# Modulo_de_expansao_01.net
KiCad netlist of a schematic drawn in EAGLE
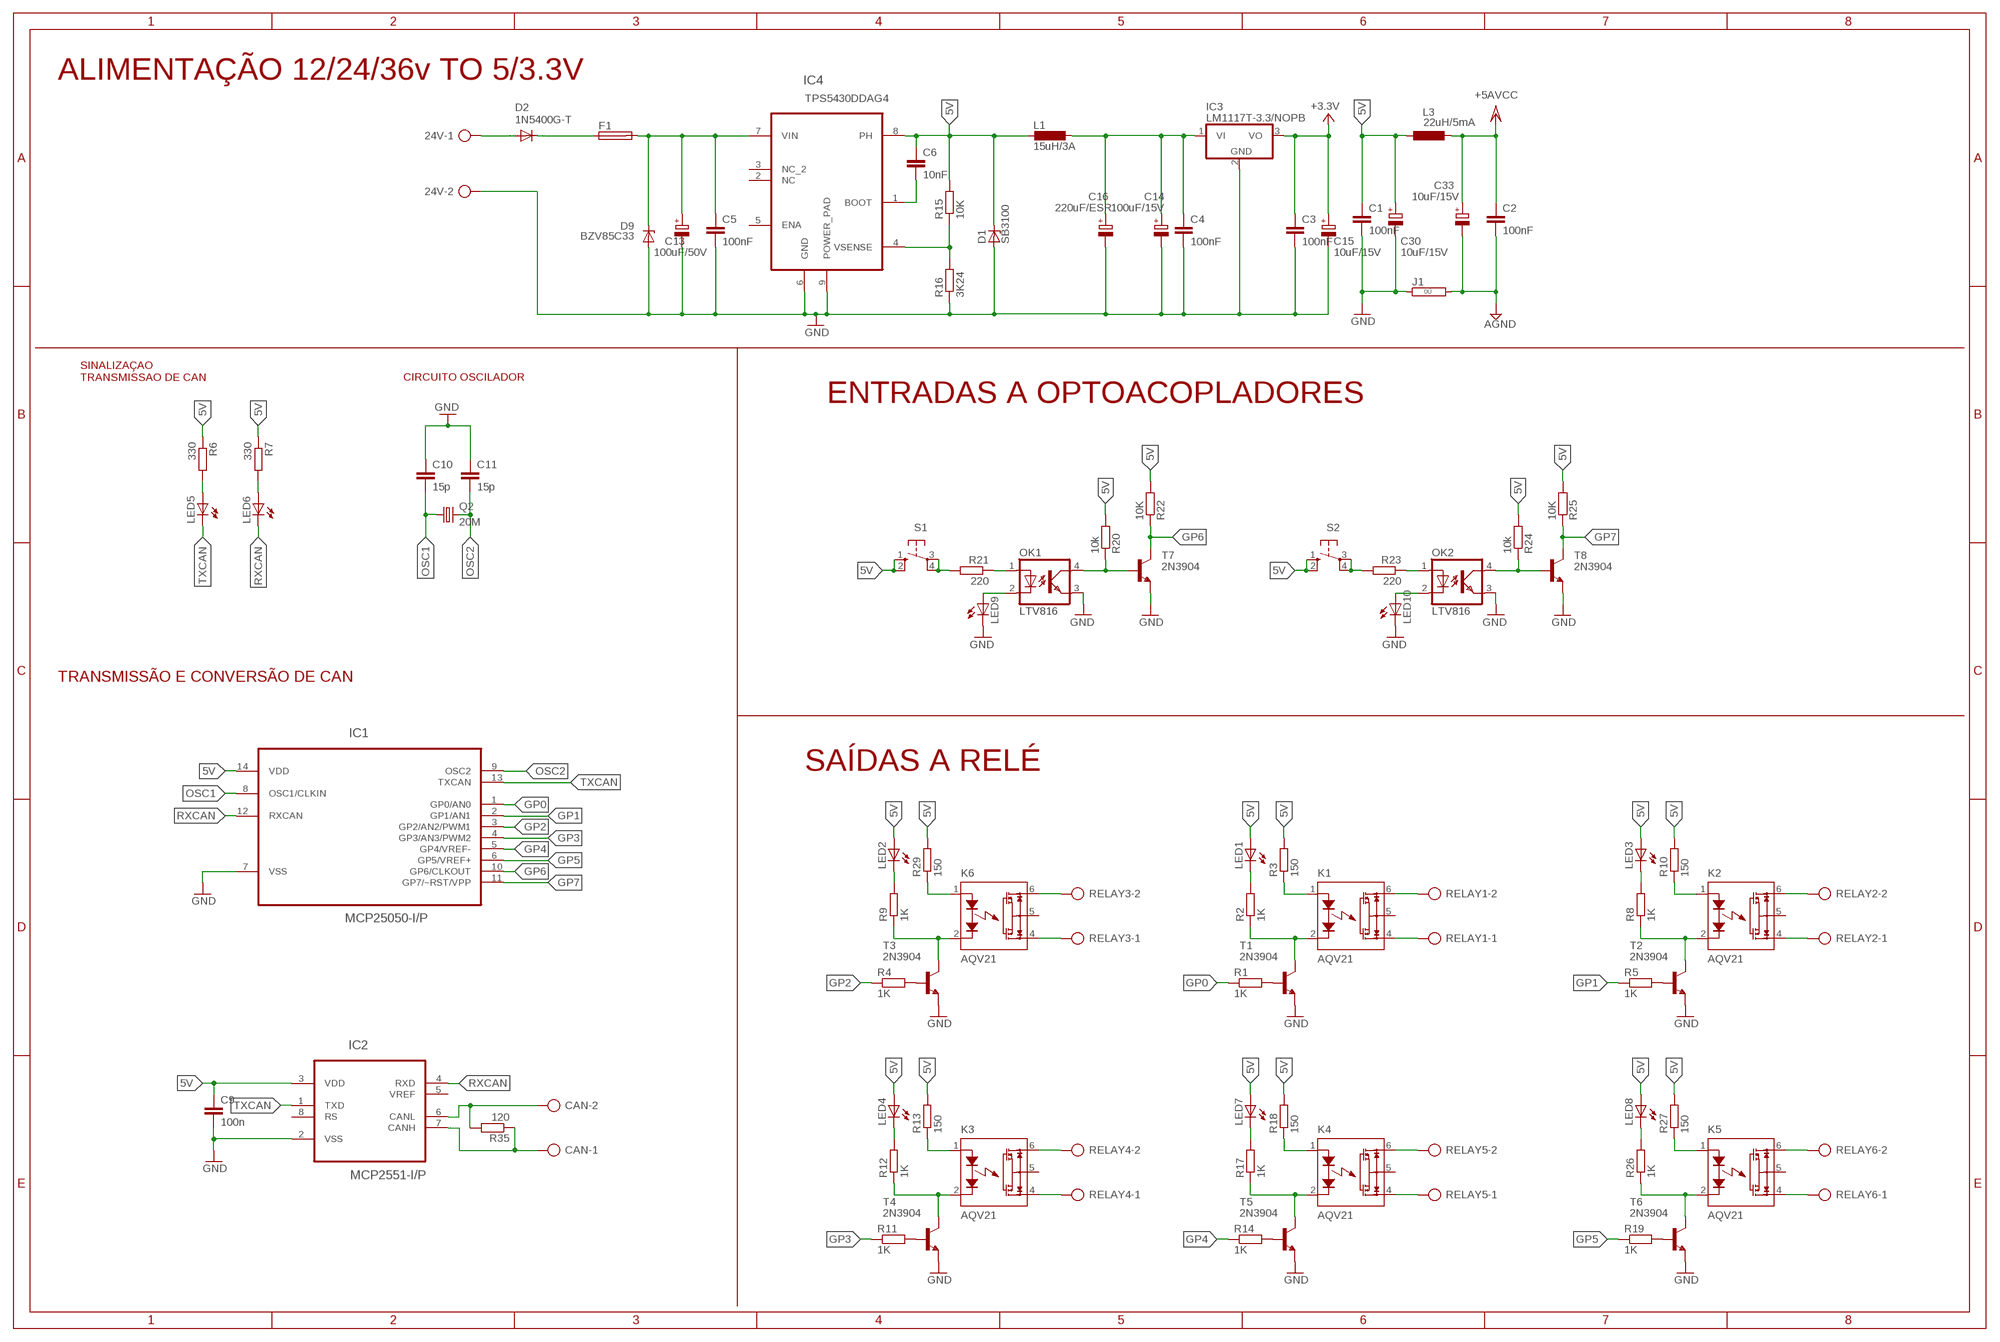
[diagram p0: schematic, sheet 1]

(export (version "E")
  (design (tool "Eeschema 10.0.6"))
  (components
    (comp (ref "24V")
      (value "AK300/2")
      (footprint "eagle-import:AK300_2")
      (libsource (lib "eagle-import") (part "AK300/2"))
    )
    (comp (ref "C1")
      (value "100nF")
      (footprint "eagle-import:C050-024X044")
      (libsource (lib "eagle-import") (part "C-EU050-024X044"))
    )
    (comp (ref "C2")
      (value "100nF")
      (footprint "eagle-import:C050-024X044")
      (libsource (lib "eagle-import") (part "C-EU050-024X044"))
    )
    (comp (ref "C3")
      (value "100nF")
      (footprint "eagle-import:C050-024X044")
      (libsource (lib "eagle-import") (part "C-EU050-024X044"))
    )
    (comp (ref "C4")
      (value "100nF")
      (footprint "eagle-import:C050-024X044")
      (libsource (lib "eagle-import") (part "C-EU050-024X044"))
    )
    (comp (ref "C5")
      (value "100nF")
      (footprint "eagle-import:C050-024X044")
      (libsource (lib "eagle-import") (part "C-EU050-024X044"))
    )
    (comp (ref "C6")
      (value "10nF")
      (footprint "eagle-import:C025-025X050")
      (libsource (lib "eagle-import") (part "C-EU025-025X050"))
    )
    (comp (ref "C9")
      (value "100n")
      (footprint "eagle-import:C050-024X044")
      (libsource (lib "eagle-import") (part "C-EU050-024X044"))
    )
    (comp (ref "C10")
      (value "15p")
      (footprint "eagle-import:C025-024X044")
      (libsource (lib "eagle-import") (part "C-EU025-024X044"))
    )
    (comp (ref "C11")
      (value "15p")
      (footprint "eagle-import:C025-024X044")
      (libsource (lib "eagle-import") (part "C-EU025-024X044"))
    )
    (comp (ref "C13")
      (value "100uF/50V")
      (footprint "eagle-import:E3,5-10")
      (libsource (lib "eagle-import") (part "CPOL-EUE3.5-10"))
    )
    (comp (ref "C14")
      (value "100uF/15V")
      (footprint "eagle-import:E2-5")
      (libsource (lib "eagle-import") (part "CPOL-EUE2-5"))
    )
    (comp (ref "C15")
      (value "10uF/15V")
      (footprint "eagle-import:E2-5")
      (libsource (lib "eagle-import") (part "CPOL-EUE2-5"))
    )
    (comp (ref "C16")
      (value "220uF/ESR")
      (footprint "eagle-import:E2,5-7")
      (libsource (lib "eagle-import") (part "CPOL-EUE2.5-7"))
    )
    (comp (ref "C30")
      (value "10uF/15V")
      (footprint "eagle-import:E2,5-6")
      (libsource (lib "eagle-import") (part "CPOL-EUE2.5-6"))
    )
    (comp (ref "C33")
      (value "10uF/15V")
      (footprint "eagle-import:E2,5-6")
      (libsource (lib "eagle-import") (part "CPOL-EUE2.5-6"))
    )
    (comp (ref "CAN")
      (value "AK300/2")
      (footprint "eagle-import:AK300_2")
      (libsource (lib "eagle-import") (part "AK300/2"))
    )
    (comp (ref "D1")
      (value "SB3100")
      (footprint "eagle-import:DO34Z7")
      (libsource (lib "eagle-import") (part "BZV10"))
    )
    (comp (ref "D2")
      (value "1N5400G-T")
      (footprint "eagle-import:DO07")
      (libsource (lib "eagle-import") (part "AA112"))
    )
    (comp (ref "D9")
      (value "BZV85C33")
      (footprint "eagle-import:DO34Z7")
      (libsource (lib "eagle-import") (part "BZV10"))
    )
    (comp (ref "F1")
      (value "TR5")
      (footprint "eagle-import:TR5")
      (libsource (lib "eagle-import") (part "TR5"))
    )
    (comp (ref "IC1")
      (value "MCP25050-I/P")
      (footprint "eagle-import:DIP254P762X432-14")
      (libsource (lib "eagle-import") (part "MCP25050-I/P"))
    )
    (comp (ref "IC2")
      (value "MCP2551-I/P")
      (footprint "eagle-import:DIP254P762X432-8")
      (libsource (lib "eagle-import") (part "MCP2551-I/P"))
    )
    (comp (ref "IC3")
      (value "LM1117T-3.3/NOPB")
      (footprint "eagle-import:TO220H")
      (libsource (lib "eagle-import") (part "LM340?-H12"))
    )
    (comp (ref "IC4")
      (value "TPS5430DDAG4")
      (footprint "eagle-import:SOIC127P600X170-9N")
      (fields (field (name "MPN") "TPS5430DDAG4"))
      (libsource (lib "eagle-import") (part "TPS5430DDAG4"))
    )
    (comp (ref "J1")
      (value "0R")
      (footprint "eagle-import:0R_10")
      (libsource (lib "eagle-import") (part "0R"))
    )
    (comp (ref "K1")
      (value "AQV21")
      (footprint "eagle-import:DIL06")
      (fields (field (name "MPN") "AQV210"))
      (libsource (lib "eagle-import") (part "AQV21"))
    )
    (comp (ref "K2")
      (value "AQV21")
      (footprint "eagle-import:DIL06")
      (fields (field (name "MPN") "AQV210"))
      (libsource (lib "eagle-import") (part "AQV21"))
    )
    (comp (ref "K3")
      (value "AQV21")
      (footprint "eagle-import:DIL06")
      (fields (field (name "MPN") "AQV210"))
      (libsource (lib "eagle-import") (part "AQV21"))
    )
    (comp (ref "K4")
      (value "AQV21")
      (footprint "eagle-import:DIL06")
      (fields (field (name "MPN") "AQV210"))
      (libsource (lib "eagle-import") (part "AQV21"))
    )
    (comp (ref "K5")
      (value "AQV21")
      (footprint "eagle-import:DIL06")
      (fields (field (name "MPN") "AQV210"))
      (libsource (lib "eagle-import") (part "AQV21"))
    )
    (comp (ref "K6")
      (value "AQV21")
      (footprint "eagle-import:DIL06")
      (fields (field (name "MPN") "AQV210"))
      (libsource (lib "eagle-import") (part "AQV21"))
    )
    (comp (ref "L1")
      (value "15uH/3A")
      (footprint "eagle-import:6000-XXXX-RC")
      (libsource (lib "eagle-import") (part "L-EU6000-XXX-RC"))
    )
    (comp (ref "L3")
      (value "22uH/5mA")
      (footprint "eagle-import:6000-XXXX-RC")
      (libsource (lib "eagle-import") (part "L-EU6000-XXX-RC"))
    )
    (comp (ref "LED1")
      (value "LED3MM")
      (footprint "eagle-import:LED3MM")
      (libsource (lib "eagle-import") (part "LED3MM"))
    )
    (comp (ref "LED2")
      (value "LED3MM")
      (footprint "eagle-import:LED3MM")
      (libsource (lib "eagle-import") (part "LED3MM"))
    )
    (comp (ref "LED3")
      (value "LED3MM")
      (footprint "eagle-import:LED3MM")
      (libsource (lib "eagle-import") (part "LED3MM"))
    )
    (comp (ref "LED4")
      (value "LED3MM")
      (footprint "eagle-import:LED3MM")
      (libsource (lib "eagle-import") (part "LED3MM"))
    )
    (comp (ref "LED5")
      (value "LED3MM")
      (footprint "eagle-import:LED3MM")
      (libsource (lib "eagle-import") (part "LED3MM"))
    )
    (comp (ref "LED6")
      (value "LED3MM")
      (footprint "eagle-import:LED3MM")
      (libsource (lib "eagle-import") (part "LED3MM"))
    )
    (comp (ref "LED7")
      (value "LED3MM")
      (footprint "eagle-import:LED3MM")
      (libsource (lib "eagle-import") (part "LED3MM"))
    )
    (comp (ref "LED8")
      (value "LED3MM")
      (footprint "eagle-import:LED3MM")
      (libsource (lib "eagle-import") (part "LED3MM"))
    )
    (comp (ref "LED9")
      (value "LED3MM")
      (footprint "eagle-import:LED3MM")
      (libsource (lib "eagle-import") (part "LED3MM"))
    )
    (comp (ref "LED10")
      (value "LED3MM")
      (footprint "eagle-import:LED3MM")
      (libsource (lib "eagle-import") (part "LED3MM"))
    )
    (comp (ref "OK1")
      (value "LTV816")
      (footprint "eagle-import:DIL04")
      (libsource (lib "eagle-import") (part "LTV816"))
    )
    (comp (ref "OK2")
      (value "LTV816")
      (footprint "eagle-import:DIL04")
      (libsource (lib "eagle-import") (part "LTV816"))
    )
    (comp (ref "Q2")
      (value "20M")
      (footprint "eagle-import:HC49_S")
      (libsource (lib "eagle-import") (part "CRYSTALHC49S"))
    )
    (comp (ref "R1")
      (value "1K")
      (footprint "eagle-import:0207_10")
      (libsource (lib "eagle-import") (part "R-EU_0207/10"))
    )
    (comp (ref "R2")
      (value "1K")
      (footprint "eagle-import:0207_10")
      (libsource (lib "eagle-import") (part "R-EU_0207/10"))
    )
    (comp (ref "R3")
      (value "150")
      (footprint "eagle-import:0207_10")
      (libsource (lib "eagle-import") (part "R-EU_0207/10"))
    )
    (comp (ref "R4")
      (value "1K")
      (footprint "eagle-import:0207_10")
      (libsource (lib "eagle-import") (part "R-EU_0207/10"))
    )
    (comp (ref "R5")
      (value "1K")
      (footprint "eagle-import:0207_10")
      (libsource (lib "eagle-import") (part "R-EU_0207/10"))
    )
    (comp (ref "R6")
      (value "330")
      (footprint "eagle-import:0207_10")
      (libsource (lib "eagle-import") (part "R-EU_0207/10"))
    )
    (comp (ref "R7")
      (value "330")
      (footprint "eagle-import:0207_10")
      (libsource (lib "eagle-import") (part "R-EU_0207/10"))
    )
    (comp (ref "R8")
      (value "1K")
      (footprint "eagle-import:0207_10")
      (libsource (lib "eagle-import") (part "R-EU_0207/10"))
    )
    (comp (ref "R9")
      (value "1K")
      (footprint "eagle-import:0207_10")
      (libsource (lib "eagle-import") (part "R-EU_0207/10"))
    )
    (comp (ref "R10")
      (value "150")
      (footprint "eagle-import:0207_10")
      (libsource (lib "eagle-import") (part "R-EU_0207/10"))
    )
    (comp (ref "R11")
      (value "1K")
      (footprint "eagle-import:0207_10")
      (libsource (lib "eagle-import") (part "R-EU_0207/10"))
    )
    (comp (ref "R12")
      (value "1K")
      (footprint "eagle-import:0207_10")
      (libsource (lib "eagle-import") (part "R-EU_0207/10"))
    )
    (comp (ref "R13")
      (value "150")
      (footprint "eagle-import:0207_10")
      (libsource (lib "eagle-import") (part "R-EU_0207/10"))
    )
    (comp (ref "R14")
      (value "1K")
      (footprint "eagle-import:0207_10")
      (libsource (lib "eagle-import") (part "R-EU_0207/10"))
    )
    (comp (ref "R15")
      (value "10K")
      (footprint "eagle-import:0207_10")
      (libsource (lib "eagle-import") (part "R-EU_0207/10"))
    )
    (comp (ref "R16")
      (value "3K24")
      (footprint "eagle-import:0207_10")
      (libsource (lib "eagle-import") (part "R-EU_0207/10"))
    )
    (comp (ref "R17")
      (value "1K")
      (footprint "eagle-import:0207_10")
      (libsource (lib "eagle-import") (part "R-EU_0207/10"))
    )
    (comp (ref "R18")
      (value "150")
      (footprint "eagle-import:0207_10")
      (libsource (lib "eagle-import") (part "R-EU_0207/10"))
    )
    (comp (ref "R19")
      (value "1K")
      (footprint "eagle-import:0207_10")
      (libsource (lib "eagle-import") (part "R-EU_0207/10"))
    )
    (comp (ref "R20")
      (value "10k")
      (footprint "eagle-import:0207_10")
      (libsource (lib "eagle-import") (part "R-EU_0207/10"))
    )
    (comp (ref "R21")
      (value "220")
      (footprint "eagle-import:0207_10")
      (libsource (lib "eagle-import") (part "R-EU_0207/10"))
    )
    (comp (ref "R22")
      (value "10K")
      (footprint "eagle-import:0207_10")
      (libsource (lib "eagle-import") (part "R-EU_0207/10"))
    )
    (comp (ref "R23")
      (value "220")
      (footprint "eagle-import:0207_10")
      (libsource (lib "eagle-import") (part "R-EU_0207/10"))
    )
    (comp (ref "R24")
      (value "10k")
      (footprint "eagle-import:0207_10")
      (libsource (lib "eagle-import") (part "R-EU_0207/10"))
    )
    (comp (ref "R25")
      (value "10K")
      (footprint "eagle-import:0207_10")
      (libsource (lib "eagle-import") (part "R-EU_0207/10"))
    )
    (comp (ref "R26")
      (value "1K")
      (footprint "eagle-import:0207_10")
      (libsource (lib "eagle-import") (part "R-EU_0207/10"))
    )
    (comp (ref "R27")
      (value "150")
      (footprint "eagle-import:0207_10")
      (libsource (lib "eagle-import") (part "R-EU_0207/10"))
    )
    (comp (ref "R29")
      (value "150")
      (footprint "eagle-import:0207_10")
      (libsource (lib "eagle-import") (part "R-EU_0207/10"))
    )
    (comp (ref "R35")
      (value "120")
      (footprint "eagle-import:0207_10")
      (libsource (lib "eagle-import") (part "R-EU_0207/10"))
    )
    (comp (ref "RELAY1")
      (value "AK300/2")
      (footprint "eagle-import:AK300_2")
      (libsource (lib "eagle-import") (part "AK300/2"))
    )
    (comp (ref "RELAY2")
      (value "AK300/2")
      (footprint "eagle-import:AK300_2")
      (libsource (lib "eagle-import") (part "AK300/2"))
    )
    (comp (ref "RELAY3")
      (value "AK300/2")
      (footprint "eagle-import:AK300_2")
      (libsource (lib "eagle-import") (part "AK300/2"))
    )
    (comp (ref "RELAY4")
      (value "AK300/2")
      (footprint "eagle-import:AK300_2")
      (libsource (lib "eagle-import") (part "AK300/2"))
    )
    (comp (ref "RELAY5")
      (value "AK300/2")
      (footprint "eagle-import:AK300_2")
      (libsource (lib "eagle-import") (part "AK300/2"))
    )
    (comp (ref "RELAY6")
      (value "AK300/2")
      (footprint "eagle-import:AK300_2")
      (libsource (lib "eagle-import") (part "AK300/2"))
    )
    (comp (ref "S1")
      (value "10-XX")
      (footprint "eagle-import:B3F-10XX")
      (fields (field (name "MPN") "B3F-1000"))
      (libsource (lib "eagle-import") (part "10-XX"))
    )
    (comp (ref "S2")
      (value "10-XX")
      (footprint "eagle-import:B3F-10XX")
      (fields (field (name "MPN") "B3F-1000"))
      (libsource (lib "eagle-import") (part "10-XX"))
    )
    (comp (ref "T1")
      (value "2N3904")
      (footprint "eagle-import:TO92")
      (libsource (lib "eagle-import") (part "2N3904"))
    )
    (comp (ref "T2")
      (value "2N3904")
      (footprint "eagle-import:TO92")
      (libsource (lib "eagle-import") (part "2N3904"))
    )
    (comp (ref "T3")
      (value "2N3904")
      (footprint "eagle-import:TO92")
      (libsource (lib "eagle-import") (part "2N3904"))
    )
    (comp (ref "T4")
      (value "2N3904")
      (footprint "eagle-import:TO92")
      (libsource (lib "eagle-import") (part "2N3904"))
    )
    (comp (ref "T5")
      (value "2N3904")
      (footprint "eagle-import:TO92")
      (libsource (lib "eagle-import") (part "2N3904"))
    )
    (comp (ref "T6")
      (value "2N3904")
      (footprint "eagle-import:TO92")
      (libsource (lib "eagle-import") (part "2N3904"))
    )
    (comp (ref "T7")
      (value "2N3904")
      (footprint "eagle-import:TO92")
      (libsource (lib "eagle-import") (part "2N3904"))
    )
    (comp (ref "T8")
      (value "2N3904")
      (footprint "eagle-import:TO92")
      (libsource (lib "eagle-import") (part "2N3904"))
    )
  )
  (nets
    (net (code "1") (name "+3.3V") (class "Default")
      (node (ref "C15") (pin "+") (pinfunction "+_+") (pintype "passive"))
      (node (ref "C3") (pin "1") (pinfunction "1_1") (pintype "passive"))
      (node (ref "IC3") (pin "3") (pinfunction "VO_3") (pintype "passive"))
    )
    (net (code "2") (name "+5AVCC") (class "Default")
      (node (ref "C2") (pin "1") (pinfunction "1_1") (pintype "passive"))
      (node (ref "C33") (pin "+") (pinfunction "+_+") (pintype "passive"))
      (node (ref "L3") (pin "2") (pinfunction "2_2") (pintype "passive"))
    )
    (net (code "3") (name "5V") (class "Default")
      (node (ref "C1") (pin "1") (pinfunction "1_1") (pintype "passive"))
      (node (ref "C30") (pin "+") (pinfunction "+_+") (pintype "passive"))
      (node (ref "C6") (pin "1") (pinfunction "1_1") (pintype "passive"))
      (node (ref "C9") (pin "1") (pinfunction "1_1") (pintype "passive"))
      (node (ref "D1") (pin "C") (pinfunction "C_C") (pintype "passive"))
      (node (ref "IC1") (pin "14") (pinfunction "VDD_14") (pintype "power_in"))
      (node (ref "IC2") (pin "3") (pinfunction "VDD_3") (pintype "power_in"))
      (node (ref "IC4") (pin "8") (pinfunction "PH_8") (pintype "input"))
      (node (ref "L1") (pin "2") (pinfunction "2_2") (pintype "passive"))
      (node (ref "L3") (pin "1") (pinfunction "1_1") (pintype "passive"))
      (node (ref "LED1") (pin "A") (pinfunction "A_A") (pintype "passive"))
      (node (ref "LED2") (pin "A") (pinfunction "A_A") (pintype "passive"))
      (node (ref "LED3") (pin "A") (pinfunction "A_A") (pintype "passive"))
      (node (ref "LED4") (pin "A") (pinfunction "A_A") (pintype "passive"))
      (node (ref "LED7") (pin "A") (pinfunction "A_A") (pintype "passive"))
      (node (ref "LED8") (pin "A") (pinfunction "A_A") (pintype "passive"))
      (node (ref "R10") (pin "2") (pinfunction "2_2") (pintype "passive"))
      (node (ref "R13") (pin "2") (pinfunction "2_2") (pintype "passive"))
      (node (ref "R15") (pin "2") (pinfunction "2_2") (pintype "passive"))
      (node (ref "R18") (pin "2") (pinfunction "2_2") (pintype "passive"))
      (node (ref "R20") (pin "2") (pinfunction "2_2") (pintype "passive"))
      (node (ref "R22") (pin "2") (pinfunction "2_2") (pintype "passive"))
      (node (ref "R24") (pin "2") (pinfunction "2_2") (pintype "passive"))
      (node (ref "R25") (pin "2") (pinfunction "2_2") (pintype "passive"))
      (node (ref "R27") (pin "2") (pinfunction "2_2") (pintype "passive"))
      (node (ref "R29") (pin "2") (pinfunction "2_2") (pintype "passive"))
      (node (ref "R3") (pin "2") (pinfunction "2_2") (pintype "passive"))
      (node (ref "R6") (pin "1") (pinfunction "1_1") (pintype "passive"))
      (node (ref "R7") (pin "1") (pinfunction "1_1") (pintype "passive"))
      (node (ref "S1") (pin "1") (pinfunction "S_1") (pintype "passive"))
      (node (ref "S1") (pin "2") (pinfunction "S1_2") (pintype "passive"))
      (node (ref "S2") (pin "1") (pinfunction "S_1") (pintype "passive"))
      (node (ref "S2") (pin "2") (pinfunction "S1_2") (pintype "passive"))
    )
    (net (code "4") (name "AGND") (class "Default")
      (node (ref "C2") (pin "2") (pinfunction "2_2") (pintype "passive"))
      (node (ref "C33") (pin "-") (pinfunction "-_-") (pintype "passive"))
      (node (ref "J1") (pin "2") (pinfunction "2_2") (pintype "passive"))
    )
    (net (code "5") (name "GND") (class "Default")
      (node (ref "24V") (pin "2") (pinfunction "KL_2") (pintype "passive"))
      (node (ref "C1") (pin "2") (pinfunction "2_2") (pintype "passive"))
      (node (ref "C10") (pin "1") (pinfunction "1_1") (pintype "passive"))
      (node (ref "C11") (pin "1") (pinfunction "1_1") (pintype "passive"))
      (node (ref "C13") (pin "-") (pinfunction "-_-") (pintype "passive"))
      (node (ref "C14") (pin "-") (pinfunction "-_-") (pintype "passive"))
      (node (ref "C15") (pin "-") (pinfunction "-_-") (pintype "passive"))
      (node (ref "C16") (pin "-") (pinfunction "-_-") (pintype "passive"))
      (node (ref "C3") (pin "2") (pinfunction "2_2") (pintype "passive"))
      (node (ref "C30") (pin "-") (pinfunction "-_-") (pintype "passive"))
      (node (ref "C4") (pin "2") (pinfunction "2_2") (pintype "passive"))
      (node (ref "C5") (pin "2") (pinfunction "2_2") (pintype "passive"))
      (node (ref "C9") (pin "2") (pinfunction "2_2") (pintype "passive"))
      (node (ref "D1") (pin "A") (pinfunction "A_A") (pintype "passive"))
      (node (ref "D9") (pin "A") (pinfunction "A_A") (pintype "passive"))
      (node (ref "IC1") (pin "7") (pinfunction "VSS_7") (pintype "passive"))
      (node (ref "IC2") (pin "2") (pinfunction "VSS_2") (pintype "power_in"))
      (node (ref "IC3") (pin "2") (pinfunction "GND_2") (pintype "passive"))
      (node (ref "IC4") (pin "6") (pinfunction "GND_6") (pintype "passive"))
      (node (ref "IC4") (pin "9") (pinfunction "POWER_PAD_9") (pintype "passive"))
      (node (ref "J1") (pin "1") (pinfunction "1_1") (pintype "passive"))
      (node (ref "LED10") (pin "K") (pinfunction "C_K") (pintype "passive"))
      (node (ref "LED9") (pin "K") (pinfunction "C_K") (pintype "passive"))
      (node (ref "OK1") (pin "3") (pinfunction "EMIT_3") (pintype "passive"))
      (node (ref "OK2") (pin "3") (pinfunction "EMIT_3") (pintype "passive"))
      (node (ref "R16") (pin "1") (pinfunction "1_1") (pintype "passive"))
      (node (ref "T1") (pin "3") (pinfunction "E_3") (pintype "passive"))
      (node (ref "T2") (pin "3") (pinfunction "E_3") (pintype "passive"))
      (node (ref "T3") (pin "3") (pinfunction "E_3") (pintype "passive"))
      (node (ref "T4") (pin "3") (pinfunction "E_3") (pintype "passive"))
      (node (ref "T5") (pin "3") (pinfunction "E_3") (pintype "passive"))
      (node (ref "T6") (pin "3") (pinfunction "E_3") (pintype "passive"))
      (node (ref "T7") (pin "3") (pinfunction "E_3") (pintype "passive"))
      (node (ref "T8") (pin "3") (pinfunction "E_3") (pintype "passive"))
    )
    (net (code "6") (name "GP0") (class "Default")
      (node (ref "IC1") (pin "1") (pinfunction "GP0/AN0_1") (pintype "bidirectional"))
      (node (ref "R1") (pin "1") (pinfunction "1_1") (pintype "passive"))
    )
    (net (code "7") (name "GP1") (class "Default")
      (node (ref "IC1") (pin "2") (pinfunction "GP1/AN1_2") (pintype "bidirectional"))
      (node (ref "R5") (pin "1") (pinfunction "1_1") (pintype "passive"))
    )
    (net (code "8") (name "GP2") (class "Default")
      (node (ref "IC1") (pin "3") (pinfunction "GP2/AN2/PWM1_3") (pintype "bidirectional"))
      (node (ref "R4") (pin "1") (pinfunction "1_1") (pintype "passive"))
    )
    (net (code "9") (name "GP3") (class "Default")
      (node (ref "IC1") (pin "4") (pinfunction "GP3/AN3/PWM2_4") (pintype "bidirectional"))
      (node (ref "R11") (pin "1") (pinfunction "1_1") (pintype "passive"))
    )
    (net (code "10") (name "GP4") (class "Default")
      (node (ref "IC1") (pin "5") (pinfunction "GP4/VREF-_5") (pintype "bidirectional"))
      (node (ref "R14") (pin "1") (pinfunction "1_1") (pintype "passive"))
    )
    (net (code "11") (name "GP5") (class "Default")
      (node (ref "IC1") (pin "6") (pinfunction "GP5/VREF+_6") (pintype "bidirectional"))
      (node (ref "R19") (pin "1") (pinfunction "1_1") (pintype "passive"))
    )
    (net (code "12") (name "GP6") (class "Default")
      (node (ref "IC1") (pin "10") (pinfunction "GP6/CLKOUT_10") (pintype "bidirectional"))
      (node (ref "R22") (pin "1") (pinfunction "1_1") (pintype "passive"))
      (node (ref "T7") (pin "1") (pinfunction "C_1") (pintype "passive"))
    )
    (net (code "13") (name "GP7") (class "Default")
      (node (ref "IC1") (pin "11") (pinfunction "GP7/~{RST/VPP}_11") (pintype "bidirectional"))
      (node (ref "R25") (pin "1") (pinfunction "1_1") (pintype "passive"))
      (node (ref "T8") (pin "1") (pinfunction "C_1") (pintype "passive"))
    )
    (net (code "14") (name "Net-(24VA-KL)") (class "Default")
      (node (ref "24V") (pin "1") (pinfunction "KL_1") (pintype "passive"))
      (node (ref "D2") (pin "A") (pinfunction "A_A") (pintype "passive"))
    )
    (net (code "15") (name "Net-(CANA-KL)") (class "Default")
      (node (ref "CAN") (pin "1") (pinfunction "KL_1") (pintype "passive"))
      (node (ref "IC2") (pin "7") (pinfunction "CANH_7") (pintype "bidirectional"))
      (node (ref "R35") (pin "1") (pinfunction "1_1") (pintype "passive"))
    )
    (net (code "16") (name "Net-(CANB-KL)") (class "Default")
      (node (ref "CAN") (pin "2") (pinfunction "KL_2") (pintype "passive"))
      (node (ref "IC2") (pin "6") (pinfunction "CANL_6") (pintype "bidirectional"))
      (node (ref "R35") (pin "2") (pinfunction "2_2") (pintype "passive"))
    )
    (net (code "17") (name "Net-(D2-PadC)") (class "Default")
      (node (ref "D2") (pin "C") (pinfunction "C_C") (pintype "passive"))
      (node (ref "F1") (pin "1") (pinfunction "1_1") (pintype "passive"))
    )
    (net (code "18") (name "Net-(IC3-VI)") (class "Default")
      (node (ref "C14") (pin "+") (pinfunction "+_+") (pintype "passive"))
      (node (ref "C16") (pin "+") (pinfunction "+_+") (pintype "passive"))
      (node (ref "C4") (pin "1") (pinfunction "1_1") (pintype "passive"))
      (node (ref "IC3") (pin "1") (pinfunction "VI_1") (pintype "input"))
      (node (ref "L1") (pin "1") (pinfunction "1_1") (pintype "passive"))
    )
    (net (code "19") (name "Net-(IC4-BOOT)") (class "Default")
      (node (ref "C6") (pin "2") (pinfunction "2_2") (pintype "passive"))
      (node (ref "IC4") (pin "1") (pinfunction "BOOT_1") (pintype "passive"))
    )
    (net (code "20") (name "Net-(IC4-VIN)") (class "Default")
      (node (ref "C13") (pin "+") (pinfunction "+_+") (pintype "passive"))
      (node (ref "C5") (pin "1") (pinfunction "1_1") (pintype "passive"))
      (node (ref "D9") (pin "C") (pinfunction "C_C") (pintype "passive"))
      (node (ref "F1") (pin "2") (pinfunction "2_2") (pintype "passive"))
      (node (ref "IC4") (pin "7") (pinfunction "VIN_7") (pintype "power_in"))
    )
    (net (code "21") (name "Net-(IC4-VSENSE)") (class "Default")
      (node (ref "IC4") (pin "4") (pinfunction "VSENSE_4") (pintype "output"))
      (node (ref "R15") (pin "1") (pinfunction "1_1") (pintype "passive"))
      (node (ref "R16") (pin "2") (pinfunction "2_2") (pintype "passive"))
    )
    (net (code "22") (name "Net-(K1-A)") (class "Default")
      (node (ref "K1") (pin "1") (pinfunction "A_1") (pintype "passive"))
      (node (ref "R3") (pin "1") (pinfunction "1_1") (pintype "passive"))
    )
    (net (code "23") (name "Net-(K1-D1)") (class "Default")
      (node (ref "K1") (pin "6") (pinfunction "D1_6") (pintype "passive"))
      (node (ref "RELAY1") (pin "2") (pinfunction "KL_2") (pintype "passive"))
    )
    (net (code "24") (name "Net-(K1-D2)") (class "Default")
      (node (ref "K1") (pin "4") (pinfunction "D2_4") (pintype "passive"))
      (node (ref "RELAY1") (pin "1") (pinfunction "KL_1") (pintype "passive"))
    )
    (net (code "25") (name "Net-(K1-K)") (class "Default")
      (node (ref "K1") (pin "2") (pinfunction "K_2") (pintype "passive"))
      (node (ref "R2") (pin "1") (pinfunction "1_1") (pintype "passive"))
      (node (ref "T1") (pin "1") (pinfunction "C_1") (pintype "passive"))
    )
    (net (code "26") (name "Net-(K2-A)") (class "Default")
      (node (ref "K2") (pin "1") (pinfunction "A_1") (pintype "passive"))
      (node (ref "R10") (pin "1") (pinfunction "1_1") (pintype "passive"))
    )
    (net (code "27") (name "Net-(K2-D1)") (class "Default")
      (node (ref "K2") (pin "6") (pinfunction "D1_6") (pintype "passive"))
      (node (ref "RELAY2") (pin "2") (pinfunction "KL_2") (pintype "passive"))
    )
    (net (code "28") (name "Net-(K2-D2)") (class "Default")
      (node (ref "K2") (pin "4") (pinfunction "D2_4") (pintype "passive"))
      (node (ref "RELAY2") (pin "1") (pinfunction "KL_1") (pintype "passive"))
    )
    (net (code "29") (name "Net-(K2-K)") (class "Default")
      (node (ref "K2") (pin "2") (pinfunction "K_2") (pintype "passive"))
      (node (ref "R8") (pin "1") (pinfunction "1_1") (pintype "passive"))
      (node (ref "T2") (pin "1") (pinfunction "C_1") (pintype "passive"))
    )
    (net (code "30") (name "Net-(K3-A)") (class "Default")
      (node (ref "K3") (pin "1") (pinfunction "A_1") (pintype "passive"))
      (node (ref "R13") (pin "1") (pinfunction "1_1") (pintype "passive"))
    )
    (net (code "31") (name "Net-(K3-D1)") (class "Default")
      (node (ref "K3") (pin "6") (pinfunction "D1_6") (pintype "passive"))
      (node (ref "RELAY4") (pin "2") (pinfunction "KL_2") (pintype "passive"))
    )
    (net (code "32") (name "Net-(K3-D2)") (class "Default")
      (node (ref "K3") (pin "4") (pinfunction "D2_4") (pintype "passive"))
      (node (ref "RELAY4") (pin "1") (pinfunction "KL_1") (pintype "passive"))
    )
    (net (code "33") (name "Net-(K3-K)") (class "Default")
      (node (ref "K3") (pin "2") (pinfunction "K_2") (pintype "passive"))
      (node (ref "R12") (pin "1") (pinfunction "1_1") (pintype "passive"))
      (node (ref "T4") (pin "1") (pinfunction "C_1") (pintype "passive"))
    )
    (net (code "34") (name "Net-(K4-A)") (class "Default")
      (node (ref "K4") (pin "1") (pinfunction "A_1") (pintype "passive"))
      (node (ref "R18") (pin "1") (pinfunction "1_1") (pintype "passive"))
    )
    (net (code "35") (name "Net-(K4-D1)") (class "Default")
      (node (ref "K4") (pin "6") (pinfunction "D1_6") (pintype "passive"))
      (node (ref "RELAY5") (pin "2") (pinfunction "KL_2") (pintype "passive"))
    )
    (net (code "36") (name "Net-(K4-D2)") (class "Default")
      (node (ref "K4") (pin "4") (pinfunction "D2_4") (pintype "passive"))
      (node (ref "RELAY5") (pin "1") (pinfunction "KL_1") (pintype "passive"))
    )
    (net (code "37") (name "Net-(K4-K)") (class "Default")
      (node (ref "K4") (pin "2") (pinfunction "K_2") (pintype "passive"))
      (node (ref "R17") (pin "1") (pinfunction "1_1") (pintype "passive"))
      (node (ref "T5") (pin "1") (pinfunction "C_1") (pintype "passive"))
    )
    (net (code "38") (name "Net-(K5-A)") (class "Default")
      (node (ref "K5") (pin "1") (pinfunction "A_1") (pintype "passive"))
      (node (ref "R27") (pin "1") (pinfunction "1_1") (pintype "passive"))
    )
    (net (code "39") (name "Net-(K5-D1)") (class "Default")
      (node (ref "K5") (pin "6") (pinfunction "D1_6") (pintype "passive"))
      (node (ref "RELAY6") (pin "2") (pinfunction "KL_2") (pintype "passive"))
    )
    (net (code "40") (name "Net-(K5-D2)") (class "Default")
      (node (ref "K5") (pin "4") (pinfunction "D2_4") (pintype "passive"))
      (node (ref "RELAY6") (pin "1") (pinfunction "KL_1") (pintype "passive"))
    )
    (net (code "41") (name "Net-(K5-K)") (class "Default")
      (node (ref "K5") (pin "2") (pinfunction "K_2") (pintype "passive"))
      (node (ref "R26") (pin "1") (pinfunction "1_1") (pintype "passive"))
      (node (ref "T6") (pin "1") (pinfunction "C_1") (pintype "passive"))
    )
    (net (code "42") (name "Net-(K6-A)") (class "Default")
      (node (ref "K6") (pin "1") (pinfunction "A_1") (pintype "passive"))
      (node (ref "R29") (pin "1") (pinfunction "1_1") (pintype "passive"))
    )
    (net (code "43") (name "Net-(K6-D1)") (class "Default")
      (node (ref "K6") (pin "6") (pinfunction "D1_6") (pintype "passive"))
      (node (ref "RELAY3") (pin "2") (pinfunction "KL_2") (pintype "passive"))
    )
    (net (code "44") (name "Net-(K6-D2)") (class "Default")
      (node (ref "K6") (pin "4") (pinfunction "D2_4") (pintype "passive"))
      (node (ref "RELAY3") (pin "1") (pinfunction "KL_1") (pintype "passive"))
    )
    (net (code "45") (name "Net-(K6-K)") (class "Default")
      (node (ref "K6") (pin "2") (pinfunction "K_2") (pintype "passive"))
      (node (ref "R9") (pin "1") (pinfunction "1_1") (pintype "passive"))
      (node (ref "T3") (pin "1") (pinfunction "C_1") (pintype "passive"))
    )
    (net (code "46") (name "Net-(LED1-C)") (class "Default")
      (node (ref "LED1") (pin "K") (pinfunction "C_K") (pintype "passive"))
      (node (ref "R2") (pin "2") (pinfunction "2_2") (pintype "passive"))
    )
    (net (code "47") (name "Net-(LED2-C)") (class "Default")
      (node (ref "LED2") (pin "K") (pinfunction "C_K") (pintype "passive"))
      (node (ref "R9") (pin "2") (pinfunction "2_2") (pintype "passive"))
    )
    (net (code "48") (name "Net-(LED3-C)") (class "Default")
      (node (ref "LED3") (pin "K") (pinfunction "C_K") (pintype "passive"))
      (node (ref "R8") (pin "2") (pinfunction "2_2") (pintype "passive"))
    )
    (net (code "49") (name "Net-(LED4-C)") (class "Default")
      (node (ref "LED4") (pin "K") (pinfunction "C_K") (pintype "passive"))
      (node (ref "R12") (pin "2") (pinfunction "2_2") (pintype "passive"))
    )
    (net (code "50") (name "Net-(LED5-PadA)") (class "Default")
      (node (ref "LED5") (pin "A") (pinfunction "A_A") (pintype "passive"))
      (node (ref "R6") (pin "2") (pinfunction "2_2") (pintype "passive"))
    )
    (net (code "51") (name "Net-(LED6-PadA)") (class "Default")
      (node (ref "LED6") (pin "A") (pinfunction "A_A") (pintype "passive"))
      (node (ref "R7") (pin "2") (pinfunction "2_2") (pintype "passive"))
    )
    (net (code "52") (name "Net-(LED7-C)") (class "Default")
      (node (ref "LED7") (pin "K") (pinfunction "C_K") (pintype "passive"))
      (node (ref "R17") (pin "2") (pinfunction "2_2") (pintype "passive"))
    )
    (net (code "53") (name "Net-(LED8-C)") (class "Default")
      (node (ref "LED8") (pin "K") (pinfunction "C_K") (pintype "passive"))
      (node (ref "R26") (pin "2") (pinfunction "2_2") (pintype "passive"))
    )
    (net (code "54") (name "Net-(OK1-A)") (class "Default")
      (node (ref "OK1") (pin "1") (pinfunction "A_1") (pintype "passive"))
      (node (ref "R21") (pin "1") (pinfunction "1_1") (pintype "passive"))
    )
    (net (code "55") (name "Net-(OK1-C)") (class "Default")
      (node (ref "LED9") (pin "A") (pinfunction "A_A") (pintype "passive"))
      (node (ref "OK1") (pin "2") (pinfunction "C_2") (pintype "passive"))
    )
    (net (code "56") (name "Net-(OK1-COL)") (class "Default")
      (node (ref "OK1") (pin "4") (pinfunction "COL_4") (pintype "passive"))
      (node (ref "R20") (pin "1") (pinfunction "1_1") (pintype "passive"))
      (node (ref "T7") (pin "2") (pinfunction "B_2") (pintype "passive"))
    )
    (net (code "57") (name "Net-(OK2-A)") (class "Default")
      (node (ref "OK2") (pin "1") (pinfunction "A_1") (pintype "passive"))
      (node (ref "R23") (pin "1") (pinfunction "1_1") (pintype "passive"))
    )
    (net (code "58") (name "Net-(OK2-C)") (class "Default")
      (node (ref "LED10") (pin "A") (pinfunction "A_A") (pintype "passive"))
      (node (ref "OK2") (pin "2") (pinfunction "C_2") (pintype "passive"))
    )
    (net (code "59") (name "Net-(OK2-COL)") (class "Default")
      (node (ref "OK2") (pin "4") (pinfunction "COL_4") (pintype "passive"))
      (node (ref "R24") (pin "1") (pinfunction "1_1") (pintype "passive"))
      (node (ref "T8") (pin "2") (pinfunction "B_2") (pintype "passive"))
    )
    (net (code "60") (name "Net-(S1-P)") (class "Default")
      (node (ref "R21") (pin "2") (pinfunction "2_2") (pintype "passive"))
      (node (ref "S1") (pin "3") (pinfunction "P_3") (pintype "passive"))
      (node (ref "S1") (pin "4") (pinfunction "P1_4") (pintype "passive"))
    )
    (net (code "61") (name "Net-(S2-P)") (class "Default")
      (node (ref "R23") (pin "2") (pinfunction "2_2") (pintype "passive"))
      (node (ref "S2") (pin "3") (pinfunction "P_3") (pintype "passive"))
      (node (ref "S2") (pin "4") (pinfunction "P1_4") (pintype "passive"))
    )
    (net (code "62") (name "Net-(T1-B)") (class "Default")
      (node (ref "R1") (pin "2") (pinfunction "2_2") (pintype "passive"))
      (node (ref "T1") (pin "2") (pinfunction "B_2") (pintype "passive"))
    )
    (net (code "63") (name "Net-(T2-B)") (class "Default")
      (node (ref "R5") (pin "2") (pinfunction "2_2") (pintype "passive"))
      (node (ref "T2") (pin "2") (pinfunction "B_2") (pintype "passive"))
    )
    (net (code "64") (name "Net-(T3-B)") (class "Default")
      (node (ref "R4") (pin "2") (pinfunction "2_2") (pintype "passive"))
      (node (ref "T3") (pin "2") (pinfunction "B_2") (pintype "passive"))
    )
    (net (code "65") (name "Net-(T4-B)") (class "Default")
      (node (ref "R11") (pin "2") (pinfunction "2_2") (pintype "passive"))
      (node (ref "T4") (pin "2") (pinfunction "B_2") (pintype "passive"))
    )
    (net (code "66") (name "Net-(T5-B)") (class "Default")
      (node (ref "R14") (pin "2") (pinfunction "2_2") (pintype "passive"))
      (node (ref "T5") (pin "2") (pinfunction "B_2") (pintype "passive"))
    )
    (net (code "67") (name "Net-(T6-B)") (class "Default")
      (node (ref "R19") (pin "2") (pinfunction "2_2") (pintype "passive"))
      (node (ref "T6") (pin "2") (pinfunction "B_2") (pintype "passive"))
    )
    (net (code "68") (name "OSC1") (class "Default")
      (node (ref "C10") (pin "2") (pinfunction "2_2") (pintype "passive"))
      (node (ref "IC1") (pin "8") (pinfunction "OSC1/CLKIN_8") (pintype "input"))
      (node (ref "Q2") (pin "1") (pinfunction "1_1") (pintype "passive"))
    )
    (net (code "69") (name "OSC2") (class "Default")
      (node (ref "C11") (pin "2") (pinfunction "2_2") (pintype "passive"))
      (node (ref "IC1") (pin "9") (pinfunction "OSC2_9") (pintype "output"))
      (node (ref "Q2") (pin "2") (pinfunction "2_2") (pintype "passive"))
    )
    (net (code "70") (name "RXCAN") (class "Default")
      (node (ref "IC1") (pin "12") (pinfunction "RXCAN_12") (pintype "input"))
      (node (ref "IC2") (pin "4") (pinfunction "RXD_4") (pintype "output"))
      (node (ref "LED6") (pin "K") (pinfunction "C_K") (pintype "passive"))
    )
    (net (code "71") (name "TXCAN") (class "Default")
      (node (ref "IC1") (pin "13") (pinfunction "TXCAN_13") (pintype "output"))
      (node (ref "IC2") (pin "1") (pinfunction "TXD_1") (pintype "input"))
      (node (ref "LED5") (pin "K") (pinfunction "C_K") (pintype "passive"))
    )
    (net (code "72") (name "unconnected-(IC2-RS-Pad8)") (class "Default")
      (node (ref "IC2") (pin "8") (pinfunction "RS_8") (pintype "input"))
    )
    (net (code "73") (name "unconnected-(IC2-VREF-Pad5)") (class "Default")
      (node (ref "IC2") (pin "5") (pinfunction "VREF_5") (pintype "output"))
    )
    (net (code "74") (name "unconnected-(IC4-ENA-Pad5)") (class "Default")
      (node (ref "IC4") (pin "5") (pinfunction "ENA_5") (pintype "input"))
    )
    (net (code "75") (name "unconnected-(IC4-NC-Pad2)") (class "Default")
      (node (ref "IC4") (pin "2") (pinfunction "NC_2") (pintype "no_connect"))
    )
    (net (code "76") (name "unconnected-(IC4-NC_2-Pad3)") (class "Default")
      (node (ref "IC4") (pin "3") (pinfunction "NC_2_3") (pintype "no_connect"))
    )
    (net (code "77") (name "unconnected-(K1-S-Pad5)") (class "Default")
      (node (ref "K1") (pin "5") (pinfunction "S_5") (pintype "passive"))
    )
    (net (code "78") (name "unconnected-(K2-S-Pad5)") (class "Default")
      (node (ref "K2") (pin "5") (pinfunction "S_5") (pintype "passive"))
    )
    (net (code "79") (name "unconnected-(K3-S-Pad5)") (class "Default")
      (node (ref "K3") (pin "5") (pinfunction "S_5") (pintype "passive"))
    )
    (net (code "80") (name "unconnected-(K4-S-Pad5)") (class "Default")
      (node (ref "K4") (pin "5") (pinfunction "S_5") (pintype "passive"))
    )
    (net (code "81") (name "unconnected-(K5-S-Pad5)") (class "Default")
      (node (ref "K5") (pin "5") (pinfunction "S_5") (pintype "passive"))
    )
    (net (code "82") (name "unconnected-(K6-S-Pad5)") (class "Default")
      (node (ref "K6") (pin "5") (pinfunction "S_5") (pintype "passive"))
    )
  )
)
